# SFPextension.net
KiCad netlist of a schematic drawn in Altium Designer
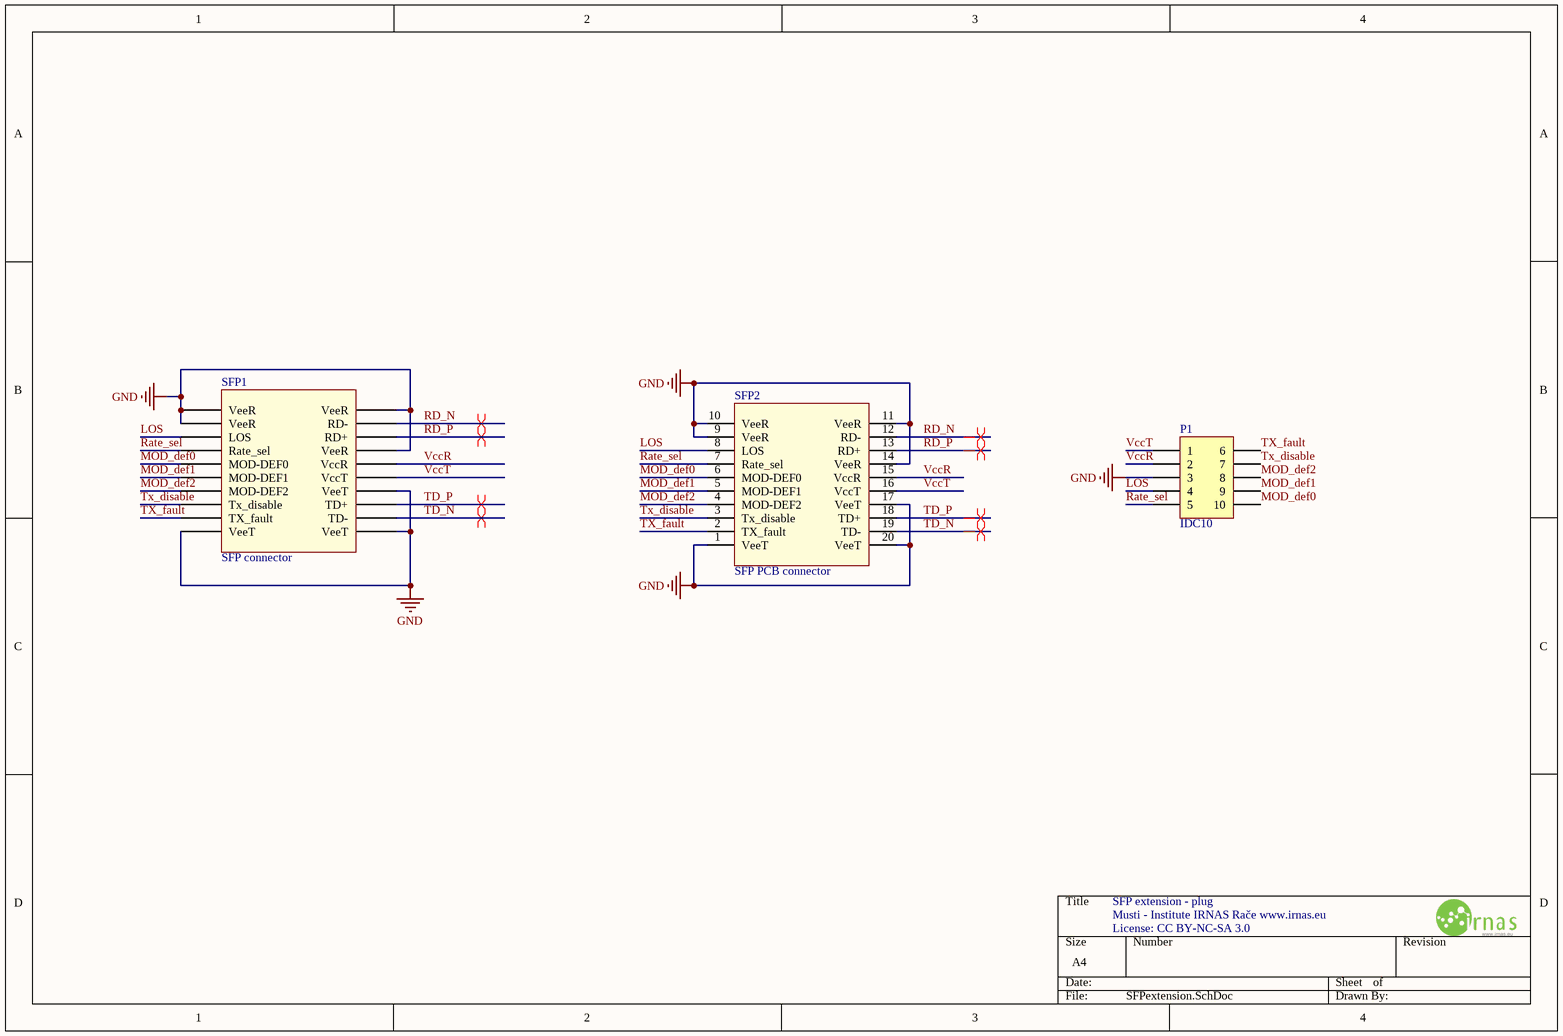
[diagram p0: SFPextension.SchDoc]

(export (version "E")
  (design (tool "Eeschema 10.0.6"))
  (components
    (comp (ref "P1")
      (value "IDC10")
      (footprint "HDR2X5_CEN")
      (description "Header, 5-Pin, Dual row")
      (libsource (lib "Miscellaneous Connectors") (part "Header 5X2A"))
    )
    (comp (ref "SFP1")
      (value "SFP connector")
      (footprint "SFP pcb con")
      (libsource (lib "GeneralComponents") (part "SFP connector"))
    )
    (comp (ref "SFP2")
      (value "SFP PCB connector")
      (footprint "SFP pcb con solder")
      (libsource (lib "SFPextension") (part "SFP PCB connector"))
    )
  )
  (nets
    (net (code "1") (name "/LOS") (class "Default")
      (node (ref "P1") (pin "4") (pinfunction "4_4") (pintype "passive"))
      (node (ref "SFP1") (pin "8") (pinfunction "LOS_8") (pintype "power_in"))
      (node (ref "SFP2") (pin "8") (pinfunction "LOS_8") (pintype "power_in"))
    )
    (net (code "2") (name "/MOD_def0") (class "Default")
      (node (ref "P1") (pin "10") (pinfunction "10_10") (pintype "passive"))
      (node (ref "SFP1") (pin "6") (pinfunction "MOD-DEF0_6") (pintype "power_in"))
      (node (ref "SFP2") (pin "6") (pinfunction "MOD-DEF0_6") (pintype "power_in"))
    )
    (net (code "3") (name "/MOD_def1") (class "Default")
      (node (ref "P1") (pin "9") (pinfunction "9_9") (pintype "passive"))
      (node (ref "SFP1") (pin "5") (pinfunction "MOD-DEF1_5") (pintype "power_in"))
      (node (ref "SFP2") (pin "5") (pinfunction "MOD-DEF1_5") (pintype "power_in"))
    )
    (net (code "4") (name "/MOD_def2") (class "Default")
      (node (ref "P1") (pin "8") (pinfunction "8_8") (pintype "passive"))
      (node (ref "SFP1") (pin "4") (pinfunction "MOD-DEF2_4") (pintype "power_in"))
      (node (ref "SFP2") (pin "4") (pinfunction "MOD-DEF2_4") (pintype "power_in"))
    )
    (net (code "5") (name "/RD_N") (class "Default")
      (node (ref "SFP1") (pin "12") (pinfunction "RD-_12") (pintype "power_in"))
      (node (ref "SFP2") (pin "12") (pinfunction "RD-_12") (pintype "power_in"))
    )
    (net (code "6") (name "/RD_P") (class "Default")
      (node (ref "SFP1") (pin "13") (pinfunction "RD+_13") (pintype "power_in"))
      (node (ref "SFP2") (pin "13") (pinfunction "RD+_13") (pintype "power_in"))
    )
    (net (code "7") (name "/Rate_sel") (class "Default")
      (node (ref "P1") (pin "5") (pinfunction "5_5") (pintype "passive"))
      (node (ref "SFP1") (pin "7") (pinfunction "Rate_sel_7") (pintype "power_in"))
      (node (ref "SFP2") (pin "7") (pinfunction "Rate_sel_7") (pintype "power_in"))
    )
    (net (code "8") (name "/TD_N") (class "Default")
      (node (ref "SFP1") (pin "19") (pinfunction "TD-_19") (pintype "power_in"))
      (node (ref "SFP2") (pin "19") (pinfunction "TD-_19") (pintype "power_in"))
    )
    (net (code "9") (name "/TD_P") (class "Default")
      (node (ref "SFP1") (pin "18") (pinfunction "TD+_18") (pintype "power_in"))
      (node (ref "SFP2") (pin "18") (pinfunction "TD+_18") (pintype "power_in"))
    )
    (net (code "10") (name "/TX_fault") (class "Default")
      (node (ref "P1") (pin "6") (pinfunction "6_6") (pintype "passive"))
      (node (ref "SFP1") (pin "2") (pinfunction "TX_fault_2") (pintype "power_in"))
      (node (ref "SFP2") (pin "2") (pinfunction "TX_fault_2") (pintype "power_in"))
    )
    (net (code "11") (name "/Tx_disable") (class "Default")
      (node (ref "P1") (pin "7") (pinfunction "7_7") (pintype "passive"))
      (node (ref "SFP1") (pin "3") (pinfunction "Tx_disable_3") (pintype "power_in"))
      (node (ref "SFP2") (pin "3") (pinfunction "Tx_disable_3") (pintype "power_in"))
    )
    (net (code "12") (name "/VccR") (class "Default")
      (node (ref "P1") (pin "2") (pinfunction "2_2") (pintype "passive"))
      (node (ref "SFP1") (pin "15") (pinfunction "VccR_15") (pintype "power_in"))
      (node (ref "SFP2") (pin "15") (pinfunction "VccR_15") (pintype "power_in"))
    )
    (net (code "13") (name "/VccT") (class "Default")
      (node (ref "P1") (pin "1") (pinfunction "1_1") (pintype "passive"))
      (node (ref "SFP1") (pin "16") (pinfunction "VccT_16") (pintype "power_in"))
      (node (ref "SFP2") (pin "16") (pinfunction "VccT_16") (pintype "power_in"))
    )
    (net (code "14") (name "GND") (class "Default")
      (node (ref "P1") (pin "3") (pinfunction "3_3") (pintype "passive"))
      (node (ref "SFP1") (pin "1") (pinfunction "VeeT_1") (pintype "power_in"))
      (node (ref "SFP1") (pin "10") (pinfunction "VeeR_10") (pintype "power_in"))
      (node (ref "SFP1") (pin "11") (pinfunction "VeeR_11") (pintype "power_in"))
      (node (ref "SFP1") (pin "14") (pinfunction "VeeR_14") (pintype "power_in"))
      (node (ref "SFP1") (pin "17") (pinfunction "VeeT_17") (pintype "power_in"))
      (node (ref "SFP1") (pin "20") (pinfunction "VeeT_20") (pintype "power_in"))
      (node (ref "SFP1") (pin "9") (pinfunction "VeeR_9") (pintype "power_in"))
      (node (ref "SFP2") (pin "1") (pinfunction "VeeT_1") (pintype "power_in"))
      (node (ref "SFP2") (pin "10") (pinfunction "VeeR_10") (pintype "power_in"))
      (node (ref "SFP2") (pin "11") (pinfunction "VeeR_11") (pintype "power_in"))
      (node (ref "SFP2") (pin "14") (pinfunction "VeeR_14") (pintype "power_in"))
      (node (ref "SFP2") (pin "17") (pinfunction "VeeT_17") (pintype "power_in"))
      (node (ref "SFP2") (pin "20") (pinfunction "VeeT_20") (pintype "power_in"))
      (node (ref "SFP2") (pin "9") (pinfunction "VeeR_9") (pintype "power_in"))
    )
  )
)
